# McPiFace-Audio-V1.net
KiCad netlist of a schematic drawn in EAGLE
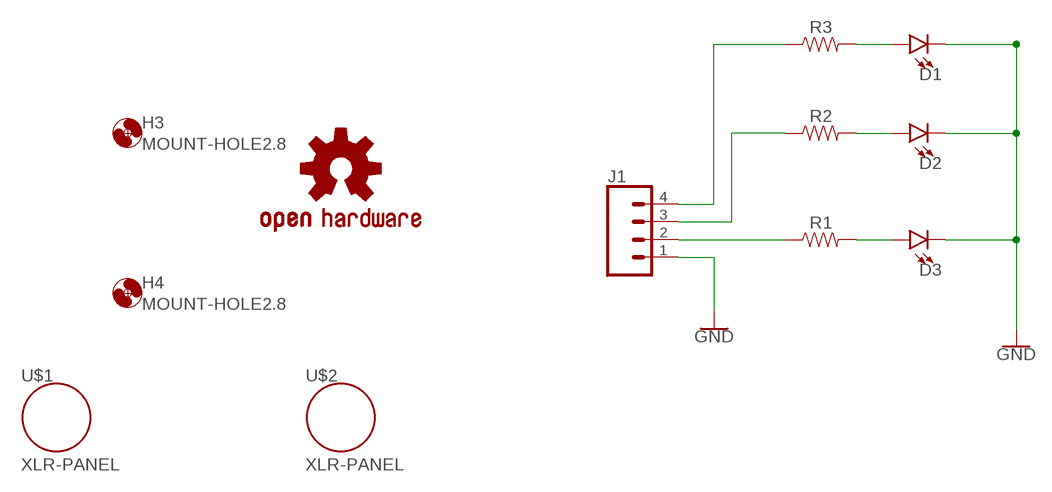
[diagram p0: schematic, sheet 1]

(export (version "E")
  (design (tool "Eeschema 10.0.6"))
  (components
    (comp (ref "D1")
      (value "LED1206-BOTTOM-1.6MM")
      (footprint "eagle-import:LED-1206-BOTTOM-1.6MM")
      (libsource (lib "eagle-import") (part "LED1206-BOTTOM-1.6MM"))
    )
    (comp (ref "D2")
      (value "LED1206-BOTTOM-1.6MM")
      (footprint "eagle-import:LED-1206-BOTTOM-1.6MM")
      (libsource (lib "eagle-import") (part "LED1206-BOTTOM-1.6MM"))
    )
    (comp (ref "D3")
      (value "LED1206-BOTTOM-1.6MM")
      (footprint "eagle-import:LED-1206-BOTTOM-1.6MM")
      (libsource (lib "eagle-import") (part "LED1206-BOTTOM-1.6MM"))
    )
    (comp (ref "H3")
      (value "MOUNT-HOLE2.8")
      (footprint "eagle-import:2,8")
      (libsource (lib "eagle-import") (part "MOUNT-HOLE2.8"))
    )
    (comp (ref "H4")
      (value "MOUNT-HOLE2.8")
      (footprint "eagle-import:2,8")
      (libsource (lib "eagle-import") (part "MOUNT-HOLE2.8"))
    )
    (comp (ref "J1")
      (value "CONN_04SMD2")
      (footprint "eagle-import:1X04_1MM_RA")
      (libsource (lib "eagle-import") (part "CONN_04SMD2"))
    )
    (comp (ref "LOGO1")
      (value "OSHW-LOGOL")
      (footprint "eagle-import:OSHW-LOGO-L")
      (libsource (lib "eagle-import") (part "OSHW-LOGOL"))
    )
    (comp (ref "R1")
      (value "RESISTOR1206")
      (footprint "eagle-import:1206")
      (libsource (lib "eagle-import") (part "RESISTOR1206"))
    )
    (comp (ref "R2")
      (value "RESISTOR1206")
      (footprint "eagle-import:1206")
      (libsource (lib "eagle-import") (part "RESISTOR1206"))
    )
    (comp (ref "R3")
      (value "RESISTOR1206")
      (footprint "eagle-import:1206")
      (libsource (lib "eagle-import") (part "RESISTOR1206"))
    )
    (comp (ref "U$1")
      (value "XLR-PANEL")
      (footprint "eagle-import:NC3FD-V-BAG-PANEL-COUTOUT")
      (libsource (lib "eagle-import") (part "XLR-PANEL"))
    )
    (comp (ref "U$2")
      (value "XLR-PANEL")
      (footprint "eagle-import:NC3FD-V-BAG-PANEL-COUTOUT")
      (libsource (lib "eagle-import") (part "XLR-PANEL"))
    )
  )
  (nets
    (net (code "1") (name "GND") (class "Default")
      (node (ref "D1") (pin "C") (pinfunction "C_C") (pintype "passive"))
      (node (ref "D2") (pin "C") (pinfunction "C_C") (pintype "passive"))
      (node (ref "D3") (pin "C") (pinfunction "C_C") (pintype "passive"))
      (node (ref "J1") (pin "1") (pinfunction "1_1") (pintype "passive"))
    )
    (net (code "2") (name "Net-(D1-PadA)") (class "Default")
      (node (ref "D1") (pin "A") (pinfunction "A_A") (pintype "passive"))
      (node (ref "R3") (pin "2") (pinfunction "2_2") (pintype "passive"))
    )
    (net (code "3") (name "Net-(D2-PadA)") (class "Default")
      (node (ref "D2") (pin "A") (pinfunction "A_A") (pintype "passive"))
      (node (ref "R2") (pin "2") (pinfunction "2_2") (pintype "passive"))
    )
    (net (code "4") (name "Net-(D3-PadA)") (class "Default")
      (node (ref "D3") (pin "A") (pinfunction "A_A") (pintype "passive"))
      (node (ref "R1") (pin "2") (pinfunction "2_2") (pintype "passive"))
    )
    (net (code "5") (name "Net-(J1-Pad2)") (class "Default")
      (node (ref "J1") (pin "2") (pinfunction "2_2") (pintype "passive"))
      (node (ref "R1") (pin "1") (pinfunction "1_1") (pintype "passive"))
    )
    (net (code "6") (name "Net-(J1-Pad3)") (class "Default")
      (node (ref "J1") (pin "3") (pinfunction "3_3") (pintype "passive"))
      (node (ref "R2") (pin "1") (pinfunction "1_1") (pintype "passive"))
    )
    (net (code "7") (name "Net-(J1-Pad4)") (class "Default")
      (node (ref "J1") (pin "4") (pinfunction "4_4") (pintype "passive"))
      (node (ref "R3") (pin "1") (pinfunction "1_1") (pintype "passive"))
    )
  )
)
